# SpeedACQ.net
KiCad netlist of a schematic drawn in Altium Designer
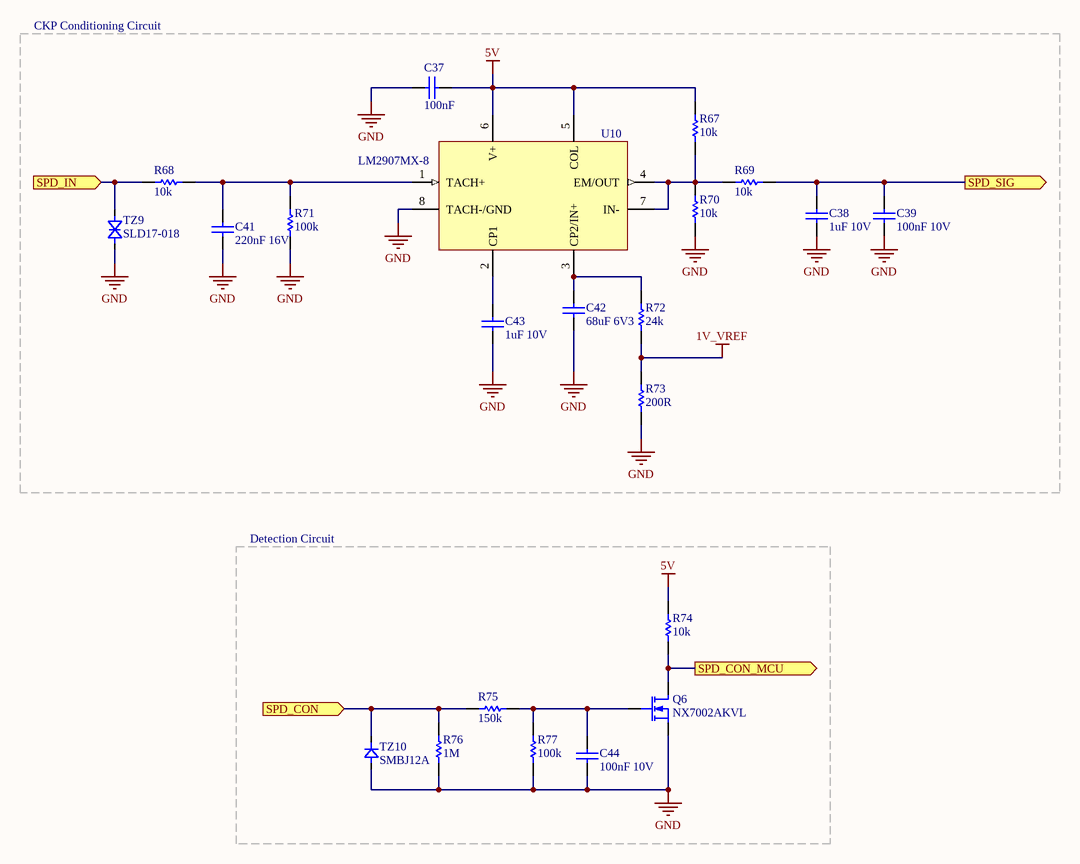
[diagram p0: SpeedACQ.SchDoc]

(export (version "E")
  (design (tool "Eeschema 10.0.6"))
  (components
    (comp (ref "C37")
      (value "100nF")
      (footprint "0402")
      (description "Capacitor")
      (fields (field (name "PARTNUMBER") "CAP.100n.10V.20%.SMD.0402") (field (name "MANUFACTURER") "Wurth"))
      (libsource (lib "IntLib") (part "Cap"))
    )
    (comp (ref "C38")
      (value "1uF 10V")
      (footprint "C0805")
      (description "Capacitor")
      (fields (field (name "PARTNUMBER") "CAP.1u.10V.5%.SMD.0805") (field (name "MANUFACTURER") "Vishay"))
      (libsource (lib "IntLib") (part "Cap"))
    )
    (comp (ref "C39")
      (value "100nF 10V")
      (footprint "0402")
      (description "Capacitor")
      (fields (field (name "PARTNUMBER") "CAP.100n.10V.20%.SMD.0402") (field (name "MANUFACTURER") "Wurth"))
      (libsource (lib "IntLib") (part "Cap"))
    )
    (comp (ref "C41")
      (value "220nF 16V")
      (footprint "0402")
      (description "Capacitor")
      (fields (field (name "PARTNUMBER") "CAP.0.22u.16V.5%.SMD.0805") (field (name "MANUFACTURER") "Wurth"))
      (libsource (lib "IntLib") (part "Cap"))
    )
    (comp (ref "C42")
      (value "68uF 6V3")
      (footprint "C0805")
      (description "Capacitor")
      (fields (field (name "PARTNUMBER") "CAP.68u.6V3.5%.SMD.0805") (field (name "MANUFACTURER") "Vishay"))
      (libsource (lib "IntLib") (part "Cap"))
    )
    (comp (ref "C43")
      (value "1uF 10V")
      (footprint "C0805")
      (description "Capacitor")
      (fields (field (name "PARTNUMBER") "CAP.1u.10V.10%.SMD.0805") (field (name "MANUFACTURER") "Vishay"))
      (libsource (lib "IntLib") (part "Cap"))
    )
    (comp (ref "C44")
      (value "100nF 10V")
      (footprint "0402")
      (description "Capacitor")
      (fields (field (name "PARTNUMBER") "CAP.100n.10V.20%.SMD.0402") (field (name "MANUFACTURER") "Wurth"))
      (libsource (lib "IntLib") (part "Cap"))
    )
    (comp (ref "Q6")
      (value "NX7002AKVL")
      (footprint "SOT23_M")
      (description "Small Signal MOSFET 60 V, 310 mA, Single, N−Channel, SOT−23")
      (fields (field (name "MANUFACTURER") "Nexperia"))
      (libsource (lib "IntLib") (part "NX7002AKVL"))
    )
    (comp (ref "R67")
      (value "10k")
      (footprint "6-0805_M")
      (description "Resistor")
      (fields (field (name "PARTNUMBER") "RES.10K.1/8W.5%.SMD.0805") (field (name "MANUFACTURER") "Yageo"))
      (libsource (lib "IntLib") (part "Res"))
    )
    (comp (ref "R68")
      (value "10k")
      (footprint "6-0805_M")
      (description "Resistor")
      (fields (field (name "PARTNUMBER") "RES.10K.1/8W.5%.SMD.0805") (field (name "MANUFACTURER") "Yageo"))
      (libsource (lib "IntLib") (part "Res"))
    )
    (comp (ref "R69")
      (value "10k")
      (footprint "6-0805_M")
      (description "Resistor")
      (fields (field (name "PARTNUMBER") "RES.10K.1/8W.5%.SMD.0805") (field (name "MANUFACTURER") "Yageo"))
      (libsource (lib "IntLib") (part "Res"))
    )
    (comp (ref "R70")
      (value "10k")
      (footprint "6-0805_M")
      (description "Resistor")
      (fields (field (name "PARTNUMBER") "RES.10K.1/8W.5%.SMD.0805") (field (name "MANUFACTURER") "Yageo"))
      (libsource (lib "IntLib") (part "Res"))
    )
    (comp (ref "R71")
      (value "100k")
      (footprint "6-0805_M")
      (description "Resistor")
      (fields (field (name "PARTNUMBER") "RES.100K.1/8W.5%.SMD.0805") (field (name "MANUFACTURER") "Yageo"))
      (libsource (lib "IntLib") (part "Res"))
    )
    (comp (ref "R72")
      (value "24k")
      (footprint "6-0805_M")
      (description "Resistor")
      (fields (field (name "PARTNUMBER") "RES.24K.1/8W.5%.SMD.0805") (field (name "MANUFACTURER") "Vishay"))
      (libsource (lib "IntLib") (part "Res"))
    )
    (comp (ref "R73")
      (value "200R")
      (footprint "6-0805_M")
      (description "Resistor")
      (fields (field (name "PARTNUMBER") "RES.200R.1/8W.1%.SMD.0805") (field (name "MANUFACTURER") "Vishay"))
      (libsource (lib "IntLib") (part "Res"))
    )
    (comp (ref "R74")
      (value "10k")
      (footprint "6-0805_M")
      (description "Resistor")
      (fields (field (name "PARTNUMBER") "RES.10K.1/8W.5%.SMD.0805") (field (name "MANUFACTURER") "Yageo"))
      (libsource (lib "IntLib") (part "Res"))
    )
    (comp (ref "R75")
      (value "150k")
      (footprint "6-0805_M")
      (description "Resistor")
      (fields (field (name "PARTNUMBER") "RES.150K.1/8W.5%.SMD.0805") (field (name "MANUFACTURER") "Vishay"))
      (libsource (lib "IntLib") (part "Res"))
    )
    (comp (ref "R76")
      (value "1M")
      (footprint "6-0805_M")
      (description "Resistor")
      (fields (field (name "PARTNUMBER") "RES.1M.1/8W.5%.SMD.0805") (field (name "MANUFACTURER") "Bourns"))
      (libsource (lib "IntLib") (part "Res"))
    )
    (comp (ref "R77")
      (value "100k")
      (footprint "6-0805_M")
      (description "Resistor")
      (fields (field (name "PARTNUMBER") "RES.100K.1/8W.5%.SMD.0805") (field (name "MANUFACTURER") "Yageo"))
      (libsource (lib "IntLib") (part "Res"))
    )
    (comp (ref "TZ9")
      (value "SLD17-018")
      (footprint "PIN-W2/E2.8")
      (description "TVS Bi-Directional VR=30V")
      (fields (field (name "MANUFACTURER") "Littelfuse"))
      (libsource (lib "IntLib") (part "SLD30-018"))
    )
    (comp (ref "TZ10")
      (value "SMBJ12A")
      (footprint "DO-214AA")
      (description "ESD Suppressors / TVS Diodes 12V 600W SMB Unidirectional")
      (fields (field (name "MANUFACTURER") "ON Semiconductor"))
      (libsource (lib "IntLib") (part "SMBJ12A"))
    )
    (comp (ref "U10")
      (value "LM2907MX-8")
      (footprint "SO8_M")
      (description "Voltage to Frequency & Frequency to Voltage Frequency to Voltage Converter")
      (fields (field (name "MANUFACTURER") "Texas Instruments"))
      (libsource (lib "IntLib") (part "LM2907MX-8"))
    )
  )
  (nets
    (net (code "1") (name "/SPD_CON") (class "Default")
      (node (ref "R75") (pin "1") (pinfunction "1_1") (pintype "passive"))
      (node (ref "R76") (pin "1") (pinfunction "1_1") (pintype "passive"))
      (node (ref "TZ10") (pin "2") (pinfunction "C_2") (pintype "passive"))
    )
    (net (code "2") (name "/SPD_CON_MCU") (class "Default")
      (node (ref "Q6") (pin "3") (pinfunction "D_3") (pintype "passive"))
      (node (ref "R74") (pin "1") (pinfunction "1_1") (pintype "passive"))
    )
    (net (code "3") (name "/SPD_IN") (class "Default")
      (node (ref "R68") (pin "1") (pinfunction "1_1") (pintype "passive"))
      (node (ref "TZ9") (pin "2") (pinfunction "K_2") (pintype "passive"))
    )
    (net (code "4") (name "/SPD_SIG") (class "Default")
      (node (ref "C38") (pin "2") (pinfunction "2_2") (pintype "passive"))
      (node (ref "C39") (pin "2") (pinfunction "2_2") (pintype "passive"))
      (node (ref "R69") (pin "2") (pinfunction "2_2") (pintype "passive"))
    )
    (net (code "5") (name "1V_VREF") (class "Default")
      (node (ref "R72") (pin "1") (pinfunction "1_1") (pintype "passive"))
      (node (ref "R73") (pin "2") (pinfunction "2_2") (pintype "passive"))
    )
    (net (code "6") (name "5V") (class "Default")
      (node (ref "C37") (pin "2") (pinfunction "2_2") (pintype "passive"))
      (node (ref "R67") (pin "2") (pinfunction "2_2") (pintype "passive"))
      (node (ref "R74") (pin "2") (pinfunction "2_2") (pintype "passive"))
      (node (ref "U10") (pin "5") (pinfunction "COL_5") (pintype "passive"))
      (node (ref "U10") (pin "6") (pinfunction "V+_6") (pintype "power_in"))
    )
    (net (code "7") (name "GND") (class "Default")
      (node (ref "C37") (pin "1") (pinfunction "1_1") (pintype "passive"))
      (node (ref "C38") (pin "1") (pinfunction "1_1") (pintype "passive"))
      (node (ref "C39") (pin "1") (pinfunction "1_1") (pintype "passive"))
      (node (ref "C41") (pin "1") (pinfunction "1_1") (pintype "passive"))
      (node (ref "C42") (pin "1") (pinfunction "1_1") (pintype "passive"))
      (node (ref "C43") (pin "1") (pinfunction "1_1") (pintype "passive"))
      (node (ref "C44") (pin "1") (pinfunction "1_1") (pintype "passive"))
      (node (ref "Q6") (pin "2") (pinfunction "S_2") (pintype "passive"))
      (node (ref "R70") (pin "1") (pinfunction "1_1") (pintype "passive"))
      (node (ref "R71") (pin "1") (pinfunction "1_1") (pintype "passive"))
      (node (ref "R73") (pin "1") (pinfunction "1_1") (pintype "passive"))
      (node (ref "R76") (pin "2") (pinfunction "2_2") (pintype "passive"))
      (node (ref "R77") (pin "1") (pinfunction "1_1") (pintype "passive"))
      (node (ref "TZ10") (pin "1") (pinfunction "A_1") (pintype "passive"))
      (node (ref "TZ9") (pin "1") (pinfunction "A_1") (pintype "passive"))
      (node (ref "U10") (pin "8") (pinfunction "TACH-/GND_8") (pintype "power_in"))
    )
    (net (code "8") (name "Net-(Q6-G)") (class "Default")
      (node (ref "C44") (pin "2") (pinfunction "2_2") (pintype "passive"))
      (node (ref "Q6") (pin "1") (pinfunction "G_1") (pintype "passive"))
      (node (ref "R75") (pin "2") (pinfunction "2_2") (pintype "passive"))
      (node (ref "R77") (pin "2") (pinfunction "2_2") (pintype "passive"))
    )
    (net (code "9") (name "Net-(U10-CP1)") (class "Default")
      (node (ref "C43") (pin "2") (pinfunction "2_2") (pintype "passive"))
      (node (ref "U10") (pin "2") (pinfunction "CP1_2") (pintype "passive"))
    )
    (net (code "10") (name "Net-(U10-CP2{slash}IN+)") (class "Default")
      (node (ref "C42") (pin "2") (pinfunction "2_2") (pintype "passive"))
      (node (ref "R72") (pin "2") (pinfunction "2_2") (pintype "passive"))
      (node (ref "U10") (pin "3") (pinfunction "CP2/IN+_3") (pintype "passive"))
    )
    (net (code "11") (name "Net-(U10-EM{slash}OUT)") (class "Default")
      (node (ref "R67") (pin "1") (pinfunction "1_1") (pintype "passive"))
      (node (ref "R69") (pin "1") (pinfunction "1_1") (pintype "passive"))
      (node (ref "R70") (pin "2") (pinfunction "2_2") (pintype "passive"))
      (node (ref "U10") (pin "4") (pinfunction "EM/OUT_4") (pintype "output"))
      (node (ref "U10") (pin "7") (pinfunction "IN-_7") (pintype "passive"))
    )
    (net (code "12") (name "Net-(U10-TACH+)") (class "Default")
      (node (ref "C41") (pin "2") (pinfunction "2_2") (pintype "passive"))
      (node (ref "R68") (pin "2") (pinfunction "2_2") (pintype "passive"))
      (node (ref "R71") (pin "2") (pinfunction "2_2") (pintype "passive"))
      (node (ref "U10") (pin "1") (pinfunction "TACH+_1") (pintype "input"))
    )
  )
)
